# SCH_spponpcbfin_2024-06-24.net
KiCad netlist of a schematic drawn in EasyEDA
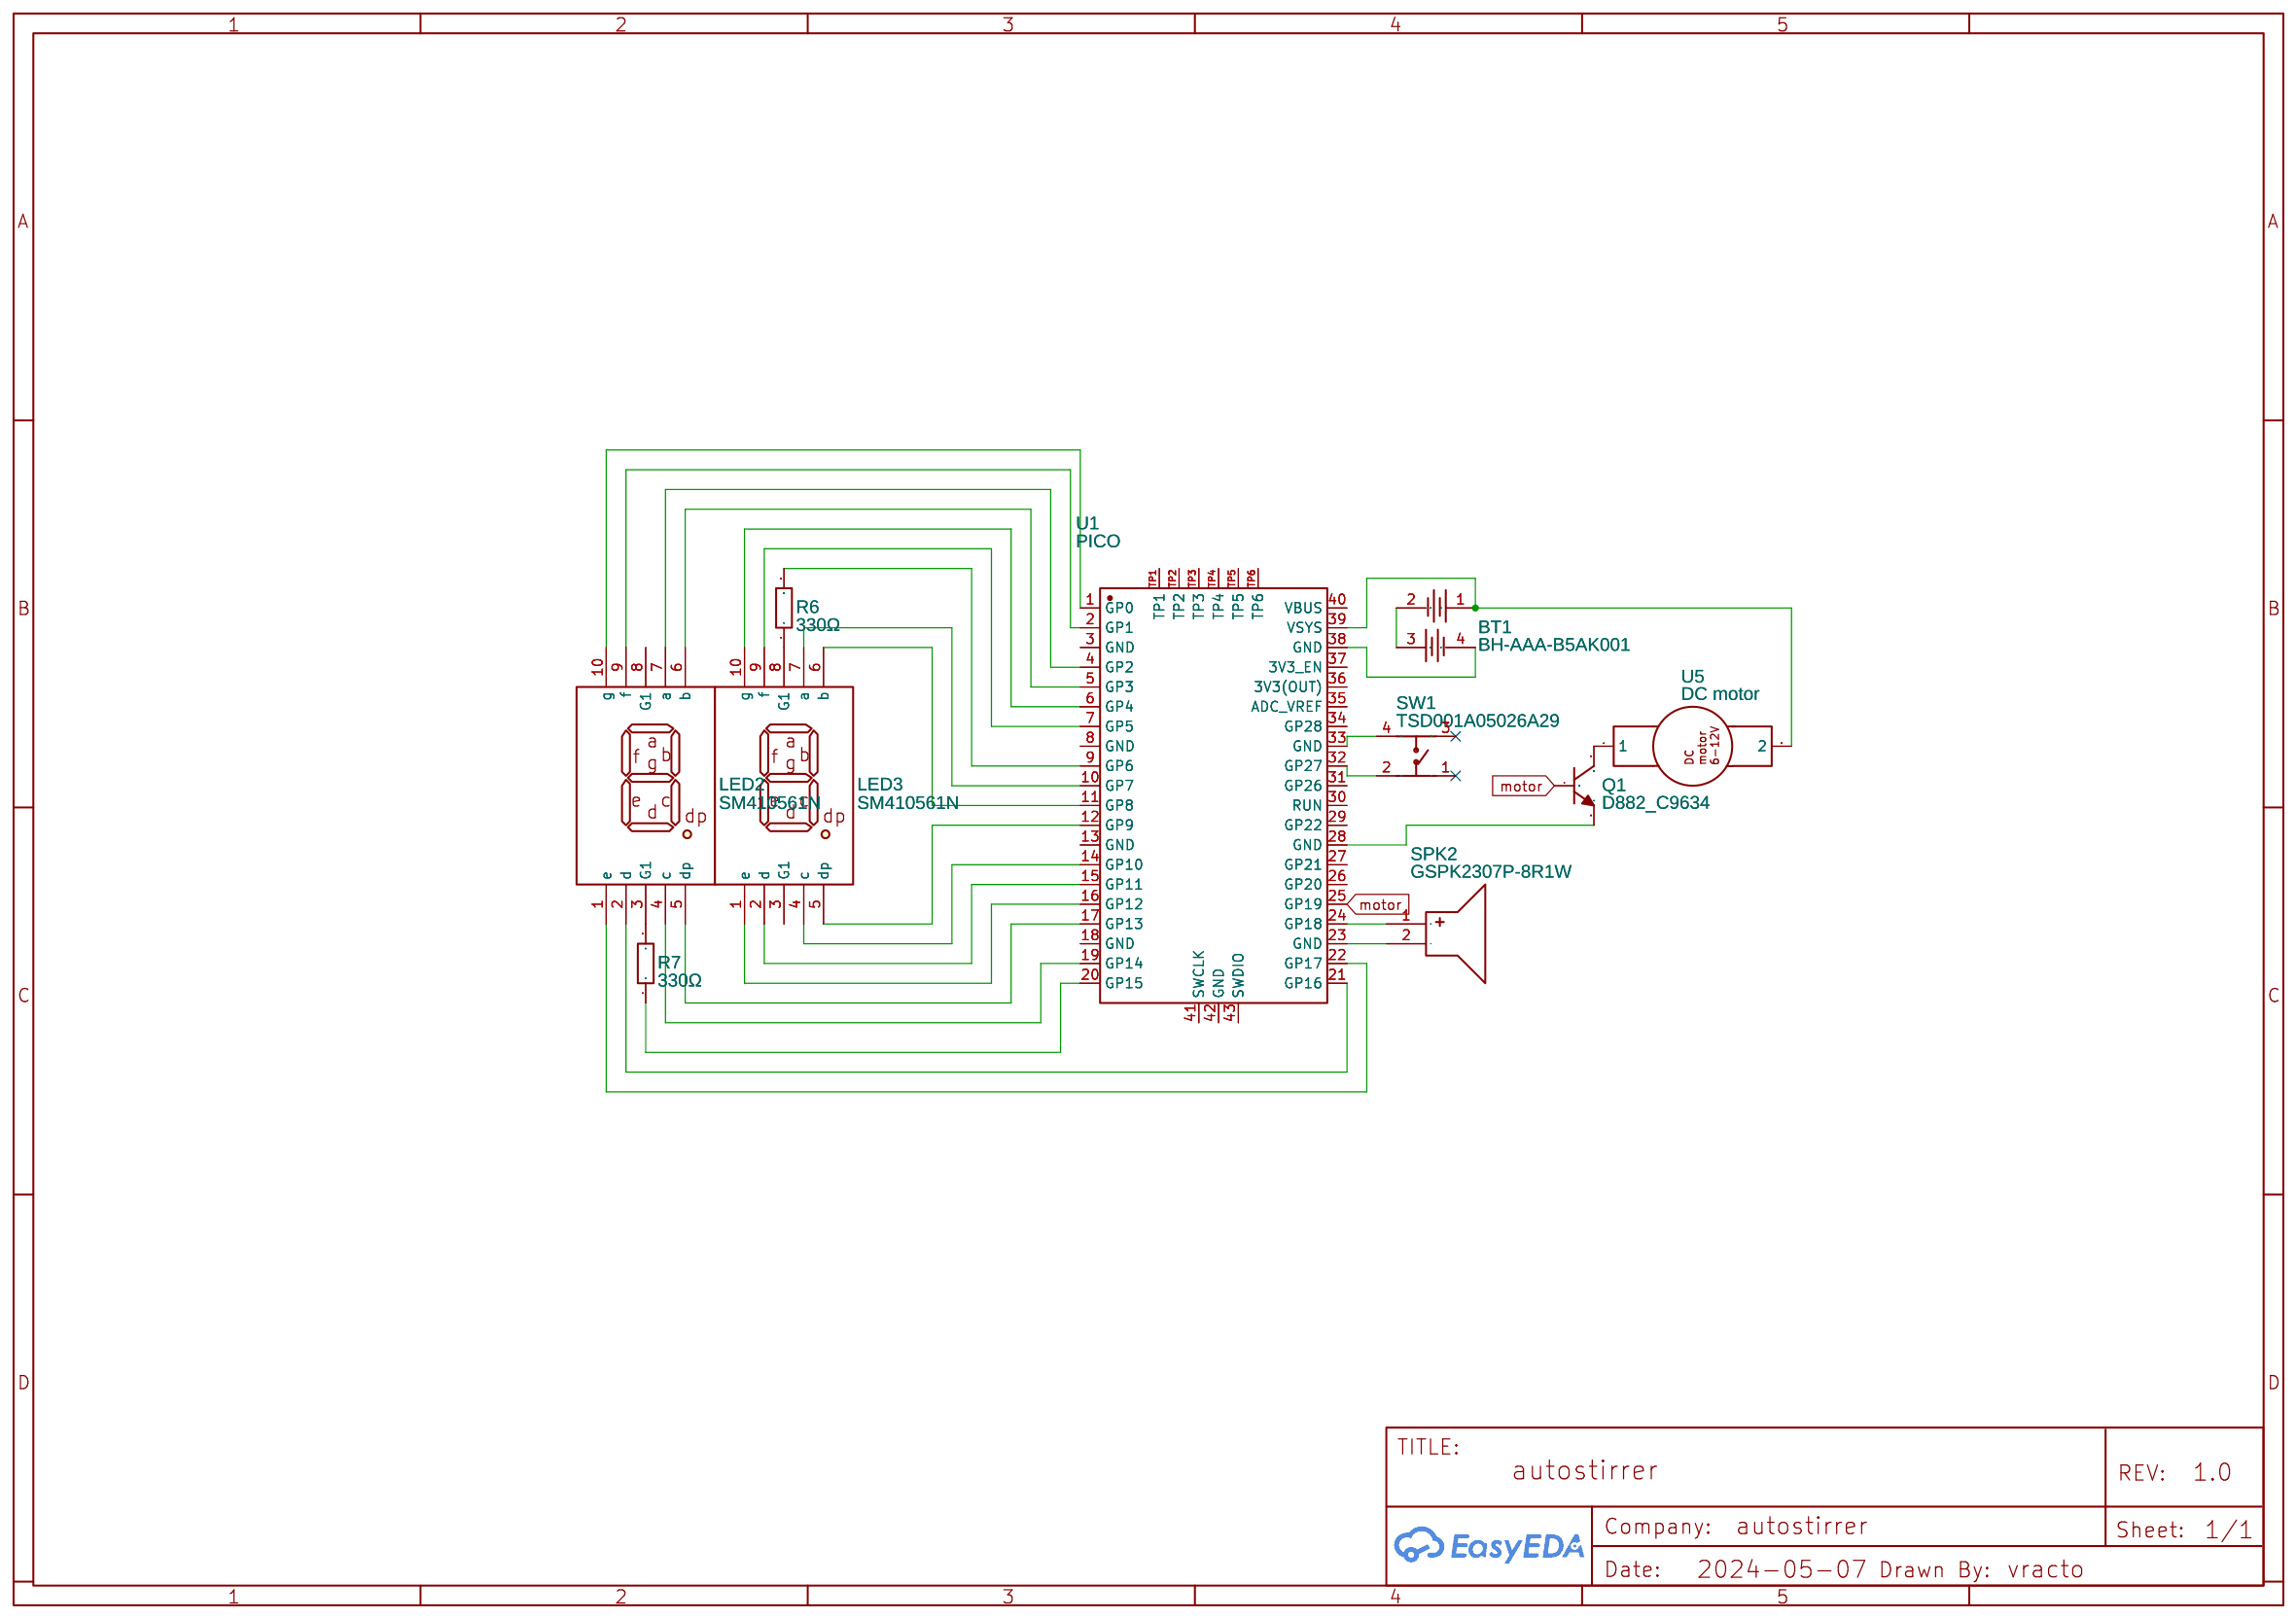
[diagram p0: schematic sheet]

(export (version "E")
  (design (tool "Eeschema 10.0.6"))
  (components
    (comp (ref "BT1")
      (value "BH-AAA-B5AK001")
      (fields (field (name "Manufacturer") "MYOUNG(美阳)"))
      (libsource (lib "") (part "BH-AAA-B5AK001"))
    )
    (comp (ref "LED2")
      (value "SM410561N")
      (fields (field (name "Manufacturer") "ARKLED(方舟)"))
      (libsource (lib "") (part "SM410561N"))
    )
    (comp (ref "LED3")
      (value "SM410561N")
      (fields (field (name "Manufacturer") "ARKLED(方舟)"))
      (libsource (lib "") (part "SM410561N"))
    )
    (comp (ref "Q1")
      (value "D882_C9634")
      (fields
        (field (name "Manufacturer Part") "D882 Y档160&#126;320")
        (field (name "Manufacturer") "CJ(江苏长电/长晶)")
      )
      (libsource (lib "") (part "D882_C9634"))
    )
    (comp (ref "R6")
      (value "330Ω")
      (fields (field (name "Manufacturer Part") "MFR-25FTE52-330R") (field (name "Manufacturer") "YAGEO(国巨)"))
      (libsource (lib "") (part "MFR-25FTE52-330R"))
    )
    (comp (ref "R7")
      (value "330Ω")
      (fields (field (name "Manufacturer Part") "MFR-25FTE52-330R") (field (name "Manufacturer") "YAGEO(国巨)"))
      (libsource (lib "") (part "MFR-25FTE52-330R"))
    )
    (comp (ref "SPK2")
      (value "GSPK2307P-8R1W")
      (fields (field (name "Manufacturer") "INGHAi(赢海)"))
      (libsource (lib "") (part "GSPK2307P-8R1W"))
    )
    (comp (ref "SW1")
      (value "TSD001A05026A29")
      (fields (field (name "Manufacturer") "BZCN(博众电气)"))
      (libsource (lib "") (part "TSD001A05026A29"))
    )
    (comp (ref "U1")
      (value "PICO")
      (fields (field (name "Manufacturer") "Raspberry Pi(树莓派)"))
      (libsource (lib "") (part "PICO"))
    )
    (comp (ref "U5")
      (value "DC motor")
      (fields (field (name "Manufacturer Part") "?"))
      (libsource (lib "") (part "Unknown_850_-435"))
    )
  )
  (nets
    (net (code "1") (name "Net-(BT1-Pad2)") (class "Default")
      (node (ref "BT1") (pin "2") (pinfunction "2_2") (pintype "input"))
      (node (ref "BT1") (pin "3") (pinfunction "3_3") (pintype "input"))
    )
    (net (code "2") (name "Net-(BT1-Pad4)") (class "Default")
      (node (ref "BT1") (pin "4") (pinfunction "4_4") (pintype "input"))
      (node (ref "U1") (pin "38") (pinfunction "GND_38") (pintype "unspecified"))
    )
    (net (code "3") (name "Net-(LED2-G1-Pad3)") (class "Default")
      (node (ref "LED2") (pin "3") (pinfunction "G1_3") (pintype "input"))
      (node (ref "R7") (pin "2") (pinfunction "2_2") (pintype "input"))
    )
    (net (code "4") (name "Net-(LED2-a)") (class "Default")
      (node (ref "LED2") (pin "7") (pinfunction "a_7") (pintype "input"))
      (node (ref "U1") (pin "4") (pinfunction "GP2_4") (pintype "unspecified"))
    )
    (net (code "5") (name "Net-(LED2-b)") (class "Default")
      (node (ref "LED2") (pin "6") (pinfunction "b_6") (pintype "input"))
      (node (ref "U1") (pin "5") (pinfunction "GP3_5") (pintype "unspecified"))
    )
    (net (code "6") (name "Net-(LED2-c)") (class "Default")
      (node (ref "LED2") (pin "4") (pinfunction "c_4") (pintype "input"))
      (node (ref "U1") (pin "19") (pinfunction "GP14_19") (pintype "unspecified"))
    )
    (net (code "7") (name "Net-(LED2-d)") (class "Default")
      (node (ref "LED2") (pin "2") (pinfunction "d_2") (pintype "input"))
      (node (ref "U1") (pin "21") (pinfunction "GP16_21") (pintype "unspecified"))
    )
    (net (code "8") (name "Net-(LED2-dp)") (class "Default")
      (node (ref "LED2") (pin "5") (pinfunction "dp_5") (pintype "input"))
      (node (ref "U1") (pin "17") (pinfunction "GP13_17") (pintype "unspecified"))
    )
    (net (code "9") (name "Net-(LED2-e)") (class "Default")
      (node (ref "LED2") (pin "1") (pinfunction "e_1") (pintype "input"))
      (node (ref "U1") (pin "22") (pinfunction "GP17_22") (pintype "unspecified"))
    )
    (net (code "10") (name "Net-(LED2-f)") (class "Default")
      (node (ref "LED2") (pin "9") (pinfunction "f_9") (pintype "input"))
      (node (ref "U1") (pin "2") (pinfunction "GP1_2") (pintype "unspecified"))
    )
    (net (code "11") (name "Net-(LED2-g)") (class "Default")
      (node (ref "LED2") (pin "10") (pinfunction "g_10") (pintype "input"))
      (node (ref "U1") (pin "1") (pinfunction "GP0_1") (pintype "unspecified"))
    )
    (net (code "12") (name "Net-(LED3-G1-Pad8)") (class "Default")
      (node (ref "LED3") (pin "8") (pinfunction "G1_8") (pintype "input"))
      (node (ref "R6") (pin "1") (pinfunction "1_1") (pintype "input"))
    )
    (net (code "13") (name "Net-(LED3-a)") (class "Default")
      (node (ref "LED3") (pin "7") (pinfunction "a_7") (pintype "input"))
      (node (ref "U1") (pin "10") (pinfunction "GP7_10") (pintype "unspecified"))
    )
    (net (code "14") (name "Net-(LED3-b)") (class "Default")
      (node (ref "LED3") (pin "6") (pinfunction "b_6") (pintype "input"))
      (node (ref "U1") (pin "11") (pinfunction "GP8_11") (pintype "unspecified"))
    )
    (net (code "15") (name "Net-(LED3-c)") (class "Default")
      (node (ref "LED3") (pin "4") (pinfunction "c_4") (pintype "input"))
      (node (ref "U1") (pin "14") (pinfunction "GP10_14") (pintype "unspecified"))
    )
    (net (code "16") (name "Net-(LED3-d)") (class "Default")
      (node (ref "LED3") (pin "2") (pinfunction "d_2") (pintype "input"))
      (node (ref "U1") (pin "15") (pinfunction "GP11_15") (pintype "unspecified"))
    )
    (net (code "17") (name "Net-(LED3-dp)") (class "Default")
      (node (ref "LED3") (pin "5") (pinfunction "dp_5") (pintype "input"))
      (node (ref "U1") (pin "12") (pinfunction "GP9_12") (pintype "unspecified"))
    )
    (net (code "18") (name "Net-(LED3-e)") (class "Default")
      (node (ref "LED3") (pin "1") (pinfunction "e_1") (pintype "input"))
      (node (ref "U1") (pin "16") (pinfunction "GP12_16") (pintype "unspecified"))
    )
    (net (code "19") (name "Net-(LED3-f)") (class "Default")
      (node (ref "LED3") (pin "9") (pinfunction "f_9") (pintype "input"))
      (node (ref "U1") (pin "7") (pinfunction "GP5_7") (pintype "unspecified"))
    )
    (net (code "20") (name "Net-(LED3-g)") (class "Default")
      (node (ref "LED3") (pin "10") (pinfunction "g_10") (pintype "input"))
      (node (ref "U1") (pin "6") (pinfunction "GP4_6") (pintype "unspecified"))
    )
    (net (code "21") (name "Net-(Q1-C)") (class "Default")
      (node (ref "Q1") (pin "2") (pinfunction "C_2") (pintype "input"))
      (node (ref "U5") (pin "1") (pinfunction "1_1") (pintype "unspecified"))
    )
    (net (code "22") (name "Net-(Q1-E)") (class "Default")
      (node (ref "Q1") (pin "3") (pinfunction "E_3") (pintype "input"))
      (node (ref "U1") (pin "28") (pinfunction "GND_28") (pintype "unspecified"))
    )
    (net (code "23") (name "Net-(SPK2-+)") (class "Default")
      (node (ref "SPK2") (pin "1") (pinfunction "+_1") (pintype "unspecified"))
      (node (ref "U1") (pin "24") (pinfunction "GP18_24") (pintype "unspecified"))
    )
    (net (code "24") (name "Net-(SPK2--)") (class "Default")
      (node (ref "SPK2") (pin "2") (pinfunction "-_2") (pintype "unspecified"))
      (node (ref "U1") (pin "23") (pinfunction "GND_23") (pintype "unspecified"))
    )
    (net (code "25") (name "Net-(SW1-Pad4)") (class "Default")
      (node (ref "SW1") (pin "4") (pinfunction "4_4") (pintype "unspecified"))
      (node (ref "U1") (pin "33") (pinfunction "GND_33") (pintype "unspecified"))
    )
    (net (code "26") (name "Net-(U1-GP6)") (class "Default")
      (node (ref "R6") (pin "2") (pinfunction "2_2") (pintype "input"))
      (node (ref "U1") (pin "9") (pinfunction "GP6_9") (pintype "unspecified"))
    )
    (net (code "27") (name "Net-(U1-GP15)") (class "Default")
      (node (ref "R7") (pin "1") (pinfunction "1_1") (pintype "input"))
      (node (ref "U1") (pin "20") (pinfunction "GP15_20") (pintype "unspecified"))
    )
    (net (code "28") (name "Net-(U1-GP27)") (class "Default")
      (node (ref "SW1") (pin "2") (pinfunction "2_2") (pintype "unspecified"))
      (node (ref "U1") (pin "32") (pinfunction "GP27_32") (pintype "unspecified"))
    )
    (net (code "29") (name "Net-(U1-VSYS)") (class "Default")
      (node (ref "BT1") (pin "1") (pinfunction "1_1") (pintype "input"))
      (node (ref "U1") (pin "39") (pinfunction "VSYS_39") (pintype "unspecified"))
      (node (ref "U5") (pin "2") (pinfunction "2_2") (pintype "unspecified"))
    )
    (net (code "30") (name "motor") (class "Default")
      (node (ref "Q1") (pin "1") (pinfunction "B_1") (pintype "input"))
      (node (ref "U1") (pin "25") (pinfunction "GP19_25") (pintype "unspecified"))
    )
    (net (code "31") (name "unconnected-(LED2-G1-Pad8)") (class "Default")
      (node (ref "LED2") (pin "8") (pinfunction "G1_8") (pintype "input"))
    )
    (net (code "32") (name "unconnected-(LED3-G1-Pad3)") (class "Default")
      (node (ref "LED3") (pin "3") (pinfunction "G1_3") (pintype "input"))
    )
    (net (code "33") (name "unconnected-(SW1-Pad1)") (class "Default")
      (node (ref "SW1") (pin "1") (pinfunction "1_1") (pintype "unspecified+no_connect"))
    )
    (net (code "34") (name "unconnected-(SW1-Pad3)") (class "Default")
      (node (ref "SW1") (pin "3") (pinfunction "3_3") (pintype "unspecified+no_connect"))
    )
    (net (code "35") (name "unconnected-(U1-3V3(OUT)-Pad36)") (class "Default")
      (node (ref "U1") (pin "36") (pinfunction "3V3(OUT)_36") (pintype "unspecified"))
    )
    (net (code "36") (name "unconnected-(U1-3V3_EN-Pad37)") (class "Default")
      (node (ref "U1") (pin "37") (pinfunction "3V3_EN_37") (pintype "unspecified"))
    )
    (net (code "37") (name "unconnected-(U1-ADC_VREF-Pad35)") (class "Default")
      (node (ref "U1") (pin "35") (pinfunction "ADC_VREF_35") (pintype "unspecified"))
    )
    (net (code "38") (name "unconnected-(U1-GND-Pad3)") (class "Default")
      (node (ref "U1") (pin "3") (pinfunction "GND_3") (pintype "unspecified"))
    )
    (net (code "39") (name "unconnected-(U1-GND-Pad8)") (class "Default")
      (node (ref "U1") (pin "8") (pinfunction "GND_8") (pintype "unspecified"))
    )
    (net (code "40") (name "unconnected-(U1-GND-Pad13)") (class "Default")
      (node (ref "U1") (pin "13") (pinfunction "GND_13") (pintype "unspecified"))
    )
    (net (code "41") (name "unconnected-(U1-GND-Pad18)") (class "Default")
      (node (ref "U1") (pin "18") (pinfunction "GND_18") (pintype "unspecified"))
    )
    (net (code "42") (name "unconnected-(U1-GND-Pad42)") (class "Default")
      (node (ref "U1") (pin "42") (pinfunction "GND_42") (pintype "unspecified"))
    )
    (net (code "43") (name "unconnected-(U1-GP20-Pad26)") (class "Default")
      (node (ref "U1") (pin "26") (pinfunction "GP20_26") (pintype "unspecified"))
    )
    (net (code "44") (name "unconnected-(U1-GP21-Pad27)") (class "Default")
      (node (ref "U1") (pin "27") (pinfunction "GP21_27") (pintype "unspecified"))
    )
    (net (code "45") (name "unconnected-(U1-GP22-Pad29)") (class "Default")
      (node (ref "U1") (pin "29") (pinfunction "GP22_29") (pintype "unspecified"))
    )
    (net (code "46") (name "unconnected-(U1-GP26-Pad31)") (class "Default")
      (node (ref "U1") (pin "31") (pinfunction "GP26_31") (pintype "unspecified"))
    )
    (net (code "47") (name "unconnected-(U1-GP28-Pad34)") (class "Default")
      (node (ref "U1") (pin "34") (pinfunction "GP28_34") (pintype "unspecified"))
    )
    (net (code "48") (name "unconnected-(U1-PadTP1)") (class "Default")
      (node (ref "U1") (pin "TP1") (pinfunction "TP1_TP1") (pintype "unspecified"))
    )
    (net (code "49") (name "unconnected-(U1-PadTP2)") (class "Default")
      (node (ref "U1") (pin "TP2") (pinfunction "TP2_TP2") (pintype "unspecified"))
    )
    (net (code "50") (name "unconnected-(U1-PadTP3)") (class "Default")
      (node (ref "U1") (pin "TP3") (pinfunction "TP3_TP3") (pintype "unspecified"))
    )
    (net (code "51") (name "unconnected-(U1-PadTP4)") (class "Default")
      (node (ref "U1") (pin "TP4") (pinfunction "TP4_TP4") (pintype "unspecified"))
    )
    (net (code "52") (name "unconnected-(U1-PadTP5)") (class "Default")
      (node (ref "U1") (pin "TP5") (pinfunction "TP5_TP5") (pintype "unspecified"))
    )
    (net (code "53") (name "unconnected-(U1-PadTP6)") (class "Default")
      (node (ref "U1") (pin "TP6") (pinfunction "TP6_TP6") (pintype "unspecified"))
    )
    (net (code "54") (name "unconnected-(U1-RUN-Pad30)") (class "Default")
      (node (ref "U1") (pin "30") (pinfunction "RUN_30") (pintype "unspecified"))
    )
    (net (code "55") (name "unconnected-(U1-SWCLK-Pad41)") (class "Default")
      (node (ref "U1") (pin "41") (pinfunction "SWCLK_41") (pintype "unspecified"))
    )
    (net (code "56") (name "unconnected-(U1-SWDIO-Pad43)") (class "Default")
      (node (ref "U1") (pin "43") (pinfunction "SWDIO_43") (pintype "unspecified"))
    )
    (net (code "57") (name "unconnected-(U1-VBUS-Pad40)") (class "Default")
      (node (ref "U1") (pin "40") (pinfunction "VBUS_40") (pintype "unspecified"))
    )
  )
)
